# jtag-adapter.net
KiCad netlist of a schematic drawn in EAGLE
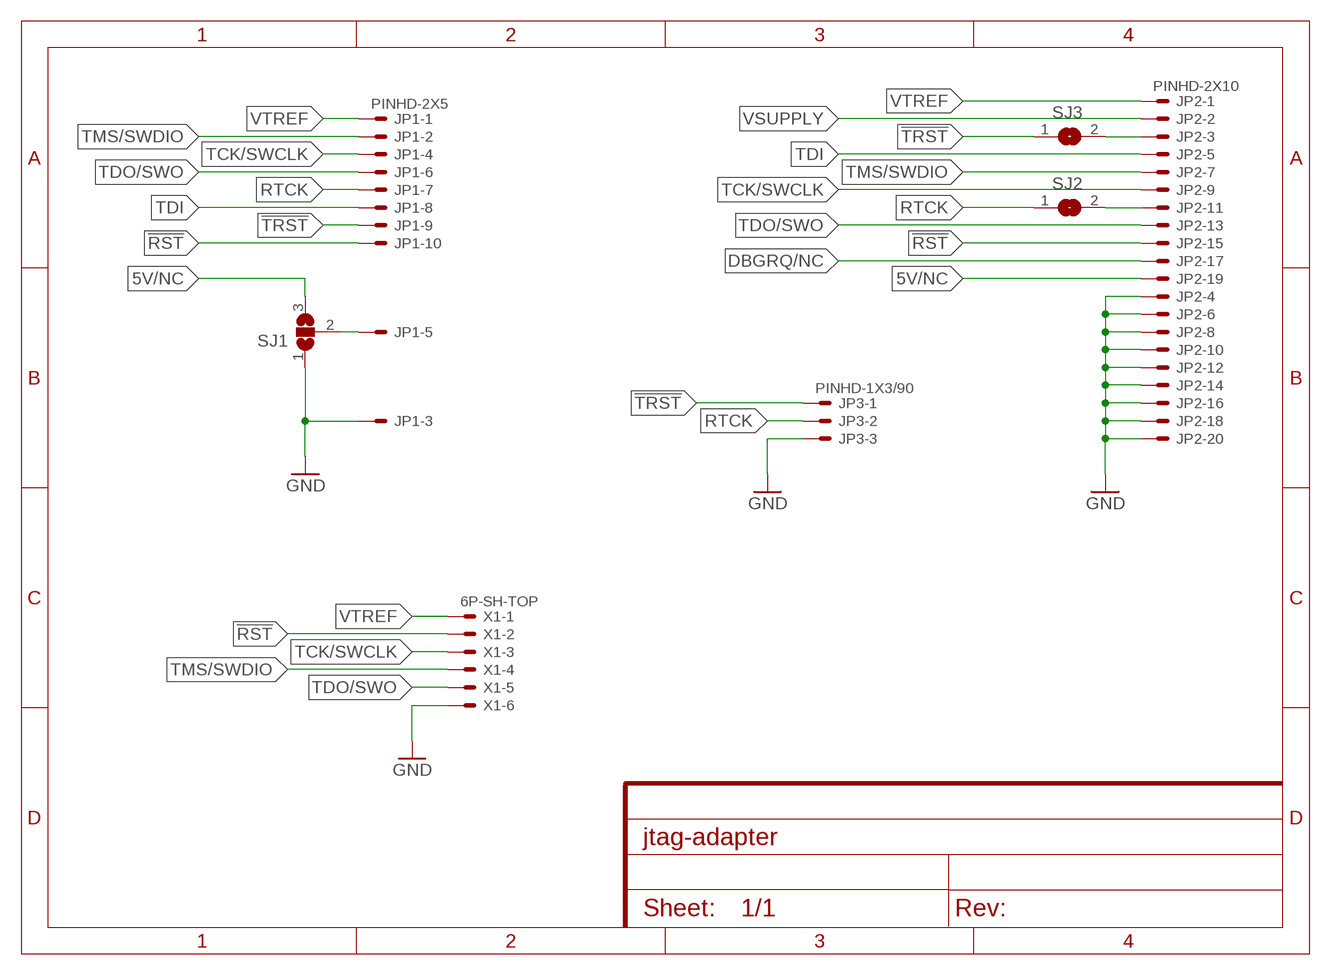
[diagram p0: schematic, sheet 1]

(export (version "E")
  (design (tool "Eeschema 10.0.6"))
  (components
    (comp (ref "JP1")
      (value "PINHD-2X5")
      (footprint "eagle-import:2X05")
      (libsource (lib "eagle-import") (part "PINHD-2X5"))
    )
    (comp (ref "JP2")
      (value "PINHD-2X10")
      (footprint "eagle-import:2X10")
      (libsource (lib "eagle-import") (part "PINHD-2X10"))
    )
    (comp (ref "JP3")
      (value "PINHD-1X3/90")
      (footprint "eagle-import:1X03_90")
      (libsource (lib "eagle-import") (part "PINHD-1X3/90"))
    )
    (comp (ref "SJ1")
      (value "SJ2S")
      (footprint "eagle-import:SJ2_S")
      (libsource (lib "eagle-import") (part "SJ2S"))
    )
    (comp (ref "SJ2")
      (value "SJS")
      (footprint "eagle-import:SJ_S")
      (libsource (lib "eagle-import") (part "SJS"))
    )
    (comp (ref "SJ3")
      (value "SJS")
      (footprint "eagle-import:SJ_S")
      (libsource (lib "eagle-import") (part "SJS"))
    )
    (comp (ref "X1")
      (value "6P-SH-TOP")
      (footprint "eagle-import:SH-06-TOP")
      (libsource (lib "eagle-import") (part "6P-SH-TOP"))
    )
  )
  (nets
    (net (code "1") (name "/~{RST}") (class "Default")
      (node (ref "JP1") (pin "10") (pinfunction "S_10") (pintype "passive"))
      (node (ref "JP2") (pin "15") (pinfunction "S_15") (pintype "passive"))
      (node (ref "X1") (pin "2") (pinfunction "S_2") (pintype "passive"))
    )
    (net (code "2") (name "/~{TRST}") (class "Default")
      (node (ref "JP1") (pin "9") (pinfunction "S_9") (pintype "passive"))
      (node (ref "JP3") (pin "1") (pinfunction "S_1") (pintype "passive"))
      (node (ref "SJ3") (pin "1") (pinfunction "1_1") (pintype "passive"))
    )
    (net (code "3") (name "5V{slash}NC") (class "Default")
      (node (ref "JP2") (pin "19") (pinfunction "S_19") (pintype "passive"))
      (node (ref "SJ1") (pin "3") (pinfunction "3_3") (pintype "passive"))
    )
    (net (code "4") (name "DBGRQ{slash}NC") (class "Default")
      (node (ref "JP2") (pin "17") (pinfunction "S_17") (pintype "passive"))
    )
    (net (code "5") (name "GND") (class "Default")
      (node (ref "JP1") (pin "3") (pinfunction "S_3") (pintype "passive"))
      (node (ref "JP2") (pin "10") (pinfunction "S_10") (pintype "passive"))
      (node (ref "JP2") (pin "12") (pinfunction "S_12") (pintype "passive"))
      (node (ref "JP2") (pin "14") (pinfunction "S_14") (pintype "passive"))
      (node (ref "JP2") (pin "16") (pinfunction "S_16") (pintype "passive"))
      (node (ref "JP2") (pin "18") (pinfunction "S_18") (pintype "passive"))
      (node (ref "JP2") (pin "20") (pinfunction "S_20") (pintype "passive"))
      (node (ref "JP2") (pin "4") (pinfunction "S_4") (pintype "passive"))
      (node (ref "JP2") (pin "6") (pinfunction "S_6") (pintype "passive"))
      (node (ref "JP2") (pin "8") (pinfunction "S_8") (pintype "passive"))
      (node (ref "JP3") (pin "3") (pinfunction "S_3") (pintype "passive"))
      (node (ref "SJ1") (pin "1") (pinfunction "1_1") (pintype "passive"))
      (node (ref "X1") (pin "6") (pinfunction "S_6") (pintype "passive"))
    )
    (net (code "6") (name "Net-(JP1F-S)") (class "Default")
      (node (ref "JP1") (pin "5") (pinfunction "S_5") (pintype "passive"))
      (node (ref "SJ1") (pin "2") (pinfunction "2_2") (pintype "passive"))
    )
    (net (code "7") (name "Net-(JP2C-S)") (class "Default")
      (node (ref "JP2") (pin "11") (pinfunction "S_11") (pintype "passive"))
      (node (ref "SJ2") (pin "2") (pinfunction "2_2") (pintype "passive"))
    )
    (net (code "8") (name "Net-(JP2N-S)") (class "Default")
      (node (ref "JP2") (pin "3") (pinfunction "S_3") (pintype "passive"))
      (node (ref "SJ3") (pin "2") (pinfunction "2_2") (pintype "passive"))
    )
    (net (code "9") (name "RTCK") (class "Default")
      (node (ref "JP1") (pin "7") (pinfunction "S_7") (pintype "passive"))
      (node (ref "JP3") (pin "2") (pinfunction "S_2") (pintype "passive"))
      (node (ref "SJ2") (pin "1") (pinfunction "1_1") (pintype "passive"))
    )
    (net (code "10") (name "TCK{slash}SWCLK") (class "Default")
      (node (ref "JP1") (pin "4") (pinfunction "S_4") (pintype "passive"))
      (node (ref "JP2") (pin "9") (pinfunction "S_9") (pintype "passive"))
      (node (ref "X1") (pin "3") (pinfunction "S_3") (pintype "passive"))
    )
    (net (code "11") (name "TDI") (class "Default")
      (node (ref "JP1") (pin "8") (pinfunction "S_8") (pintype "passive"))
      (node (ref "JP2") (pin "5") (pinfunction "S_5") (pintype "passive"))
    )
    (net (code "12") (name "TDO{slash}SWO") (class "Default")
      (node (ref "JP1") (pin "6") (pinfunction "S_6") (pintype "passive"))
      (node (ref "JP2") (pin "13") (pinfunction "S_13") (pintype "passive"))
      (node (ref "X1") (pin "5") (pinfunction "S_5") (pintype "passive"))
    )
    (net (code "13") (name "TMS{slash}SWDIO") (class "Default")
      (node (ref "JP1") (pin "2") (pinfunction "S_2") (pintype "passive"))
      (node (ref "JP2") (pin "7") (pinfunction "S_7") (pintype "passive"))
      (node (ref "X1") (pin "4") (pinfunction "S_4") (pintype "passive"))
    )
    (net (code "14") (name "VSUPPLY") (class "Default")
      (node (ref "JP2") (pin "2") (pinfunction "S_2") (pintype "passive"))
    )
    (net (code "15") (name "VTREF") (class "Default")
      (node (ref "JP1") (pin "1") (pinfunction "S_1") (pintype "passive"))
      (node (ref "JP2") (pin "1") (pinfunction "S_1") (pintype "passive"))
      (node (ref "X1") (pin "1") (pinfunction "S_1") (pintype "passive"))
    )
  )
)
